# LCD-connector.net
KiCad netlist of a schematic drawn in Altium Designer
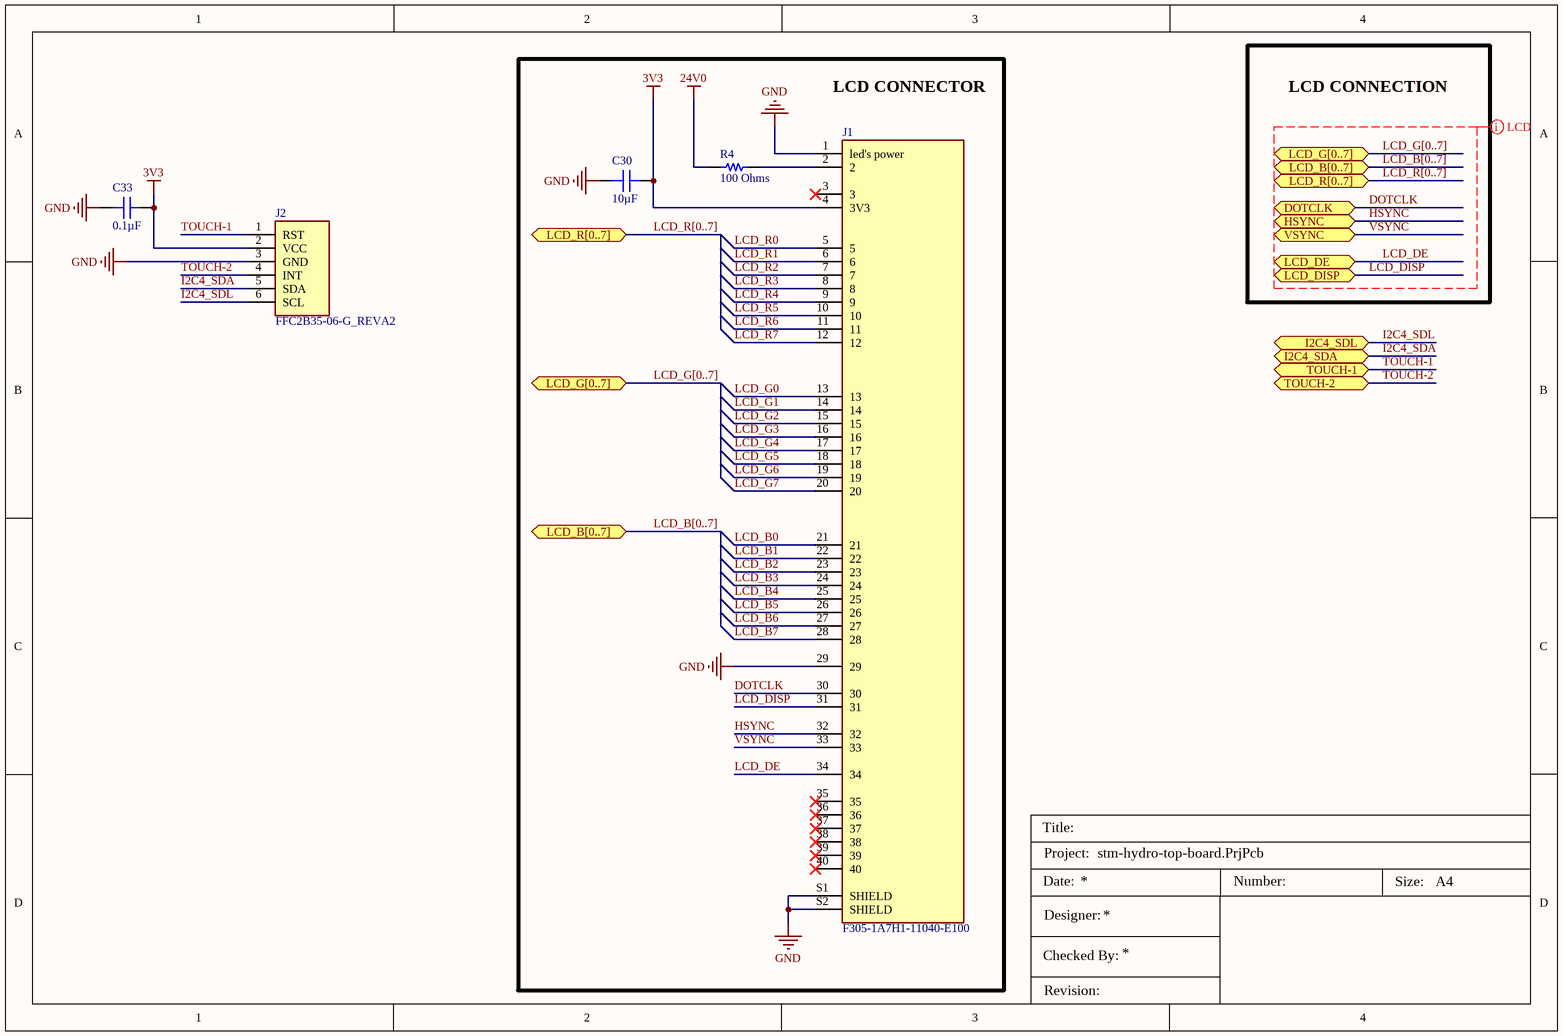
[diagram p0: LCD-connector.SchDoc]

(export (version "E")
  (design (tool "Eeschema 10.0.6"))
  (components
    (comp (ref "C30")
      (value "10µF")
      (footprint "CAP 0805_2012")
      (description "CAP CER 10UF 6.3V X5R 0805")
      (fields
        (field (name "PART NUMBER") "CL21A106MQFNNNE")
        (field (name "MANUFACTURER") "Samsung Electro-Mechanics")
      )
      (libsource (lib "Celestial Altium Library - altium_library") (part "Capacitor"))
    )
    (comp (ref "C33")
      (value "0.1µF")
      (footprint "CAP 0603_1608")
      (description "CAP CER 0.1UF 6.3V X7R 0603")
      (fields (field (name "PART NUMBER") "6R3X14W104MV4T"))
      (libsource (lib "Celestial Altium Library - altium_library") (part "Capacitor"))
    )
    (comp (ref "J1")
      (value "F305-1A7H1-11040-E100")
      (footprint "F305-1A7H1-11040-E100")
      (description "40 Position FFC, FPC Connector Contacts, Bottom 0.020\" (0.50mm) Surface Mount, Right Angle")
      (fields (field (name "MF") "Amphenol ICC (FCI)"))
      (libsource (lib "hy-smt") (part "LCD Connector"))
    )
    (comp (ref "J2")
      (value "FFC2B35-06-G_REVA2")
      (footprint "PcbLib1:GCT_FFC2B35-06-G_REVA2")
      (description "0.5mm Side entry Flat Flexible Cable Connector")
      (fields (field (name "MF") "Global Connector Technology") (field (name "MP") "FFC2B35-06-G"))
      (libsource (lib "Schlib1") (part "FFC2B35-06-G_REVA2"))
    )
    (comp (ref "R4")
      (value "100 Ohms")
      (footprint "RES 1206_3216")
      (description "RES SMD 100 OHM 1% 1/4W 1206")
      (fields
        (field (name "PART NUMBER") "CRG1206F100R")
        (field (name "MANUFACTURER") "TE Connectivity Passive Product")
      )
      (libsource (lib "Celestial Altium Library - altium_library") (part "Resistor"))
    )
  )
  (nets
    (net (code "1") (name "/DOTCLK") (class "Default")
      (node (ref "J1") (pin "30") (pinfunction "30_30") (pintype "passive"))
    )
    (net (code "2") (name "/HSYNC") (class "Default")
      (node (ref "J1") (pin "32") (pinfunction "32_32") (pintype "passive"))
    )
    (net (code "3") (name "/I2C4_SDA") (class "Default")
      (node (ref "J2") (pin "5") (pinfunction "SDA_5") (pintype "passive"))
    )
    (net (code "4") (name "/I2C4_SDL") (class "Default")
      (node (ref "J2") (pin "6") (pinfunction "SCL_6") (pintype "passive"))
    )
    (net (code "5") (name "/LCD_B0") (class "Default")
      (node (ref "J1") (pin "21") (pinfunction "21_21") (pintype "passive"))
    )
    (net (code "6") (name "/LCD_B1") (class "Default")
      (node (ref "J1") (pin "22") (pinfunction "22_22") (pintype "passive"))
    )
    (net (code "7") (name "/LCD_B2") (class "Default")
      (node (ref "J1") (pin "23") (pinfunction "23_23") (pintype "passive"))
    )
    (net (code "8") (name "/LCD_B3") (class "Default")
      (node (ref "J1") (pin "24") (pinfunction "24_24") (pintype "passive"))
    )
    (net (code "9") (name "/LCD_B4") (class "Default")
      (node (ref "J1") (pin "25") (pinfunction "25_25") (pintype "passive"))
    )
    (net (code "10") (name "/LCD_B5") (class "Default")
      (node (ref "J1") (pin "26") (pinfunction "26_26") (pintype "passive"))
    )
    (net (code "11") (name "/LCD_B6") (class "Default")
      (node (ref "J1") (pin "27") (pinfunction "27_27") (pintype "passive"))
    )
    (net (code "12") (name "/LCD_B7") (class "Default")
      (node (ref "J1") (pin "28") (pinfunction "28_28") (pintype "passive"))
    )
    (net (code "14") (name "/LCD_DE") (class "Default")
      (node (ref "J1") (pin "34") (pinfunction "34_34") (pintype "passive"))
    )
    (net (code "15") (name "/LCD_DISP") (class "Default")
      (node (ref "J1") (pin "31") (pinfunction "31_31") (pintype "passive"))
    )
    (net (code "16") (name "/LCD_G0") (class "Default")
      (node (ref "J1") (pin "13") (pinfunction "13_13") (pintype "passive"))
    )
    (net (code "17") (name "/LCD_G1") (class "Default")
      (node (ref "J1") (pin "14") (pinfunction "14_14") (pintype "passive"))
    )
    (net (code "18") (name "/LCD_G2") (class "Default")
      (node (ref "J1") (pin "15") (pinfunction "15_15") (pintype "passive"))
    )
    (net (code "19") (name "/LCD_G3") (class "Default")
      (node (ref "J1") (pin "16") (pinfunction "16_16") (pintype "passive"))
    )
    (net (code "20") (name "/LCD_G4") (class "Default")
      (node (ref "J1") (pin "17") (pinfunction "17_17") (pintype "passive"))
    )
    (net (code "21") (name "/LCD_G5") (class "Default")
      (node (ref "J1") (pin "18") (pinfunction "18_18") (pintype "passive"))
    )
    (net (code "22") (name "/LCD_G6") (class "Default")
      (node (ref "J1") (pin "19") (pinfunction "19_19") (pintype "passive"))
    )
    (net (code "23") (name "/LCD_G7") (class "Default")
      (node (ref "J1") (pin "20") (pinfunction "20_20") (pintype "passive"))
    )
    (net (code "25") (name "/LCD_R0") (class "Default")
      (node (ref "J1") (pin "5") (pinfunction "5_5") (pintype "passive"))
    )
    (net (code "26") (name "/LCD_R1") (class "Default")
      (node (ref "J1") (pin "6") (pinfunction "6_6") (pintype "passive"))
    )
    (net (code "27") (name "/LCD_R2") (class "Default")
      (node (ref "J1") (pin "7") (pinfunction "7_7") (pintype "passive"))
    )
    (net (code "28") (name "/LCD_R3") (class "Default")
      (node (ref "J1") (pin "8") (pinfunction "8_8") (pintype "passive"))
    )
    (net (code "29") (name "/LCD_R4") (class "Default")
      (node (ref "J1") (pin "9") (pinfunction "9_9") (pintype "passive"))
    )
    (net (code "30") (name "/LCD_R5") (class "Default")
      (node (ref "J1") (pin "10") (pinfunction "10_10") (pintype "passive"))
    )
    (net (code "31") (name "/LCD_R6") (class "Default")
      (node (ref "J1") (pin "11") (pinfunction "11_11") (pintype "passive"))
    )
    (net (code "32") (name "/LCD_R7") (class "Default")
      (node (ref "J1") (pin "12") (pinfunction "12_12") (pintype "passive"))
    )
    (net (code "34") (name "/TOUCH-1") (class "Default")
      (node (ref "J2") (pin "1") (pinfunction "RST_1") (pintype "passive"))
    )
    (net (code "35") (name "/TOUCH-2") (class "Default")
      (node (ref "J2") (pin "4") (pinfunction "INT_4") (pintype "passive"))
    )
    (net (code "36") (name "/VSYNC") (class "Default")
      (node (ref "J1") (pin "33") (pinfunction "33_33") (pintype "passive"))
    )
    (net (code "37") (name "3V3") (class "Default")
      (node (ref "C30") (pin "2") (pinfunction "2_2") (pintype "passive"))
      (node (ref "C33") (pin "1") (pinfunction "1_1") (pintype "passive"))
      (node (ref "J1") (pin "4") (pinfunction "3V3_4") (pintype "passive"))
      (node (ref "J2") (pin "2") (pinfunction "VCC_2") (pintype "passive"))
    )
    (net (code "38") (name "24V0") (class "Default")
      (node (ref "R4") (pin "1") (pinfunction "1_1") (pintype "passive"))
    )
    (net (code "39") (name "GND") (class "Default")
      (node (ref "C30") (pin "1") (pinfunction "1_1") (pintype "passive"))
      (node (ref "C33") (pin "2") (pinfunction "2_2") (pintype "passive"))
      (node (ref "J1") (pin "1") (pinfunction "led's_power_1") (pintype "passive"))
      (node (ref "J1") (pin "29") (pinfunction "29_29") (pintype "passive"))
      (node (ref "J1") (pin "S1") (pinfunction "SHIELD_S1") (pintype "passive"))
      (node (ref "J1") (pin "S2") (pinfunction "SHIELD_S2") (pintype "passive"))
      (node (ref "J2") (pin "3") (pinfunction "GND_3") (pintype "passive"))
    )
    (net (code "40") (name "Net-(J1-Pad2)") (class "Default")
      (node (ref "J1") (pin "2") (pinfunction "2_2") (pintype "passive"))
      (node (ref "R4") (pin "2") (pinfunction "2_2") (pintype "passive"))
    )
    (net (code "41") (name "unconnected-(J1-Pad3)") (class "Default")
      (node (ref "J1") (pin "3") (pinfunction "3_3") (pintype "passive+no_connect"))
    )
    (net (code "42") (name "unconnected-(J1-Pad35)") (class "Default")
      (node (ref "J1") (pin "35") (pinfunction "35_35") (pintype "passive+no_connect"))
    )
    (net (code "43") (name "unconnected-(J1-Pad36)") (class "Default")
      (node (ref "J1") (pin "36") (pinfunction "36_36") (pintype "passive+no_connect"))
    )
    (net (code "44") (name "unconnected-(J1-Pad37)") (class "Default")
      (node (ref "J1") (pin "37") (pinfunction "37_37") (pintype "passive+no_connect"))
    )
    (net (code "45") (name "unconnected-(J1-Pad38)") (class "Default")
      (node (ref "J1") (pin "38") (pinfunction "38_38") (pintype "passive+no_connect"))
    )
    (net (code "46") (name "unconnected-(J1-Pad39)") (class "Default")
      (node (ref "J1") (pin "39") (pinfunction "39_39") (pintype "passive+no_connect"))
    )
    (net (code "47") (name "unconnected-(J1-Pad40)") (class "Default")
      (node (ref "J1") (pin "40") (pinfunction "40_40") (pintype "passive+no_connect"))
    )
  )
)
